# design.net
KiCad netlist of a schematic drawn in Altium Designer
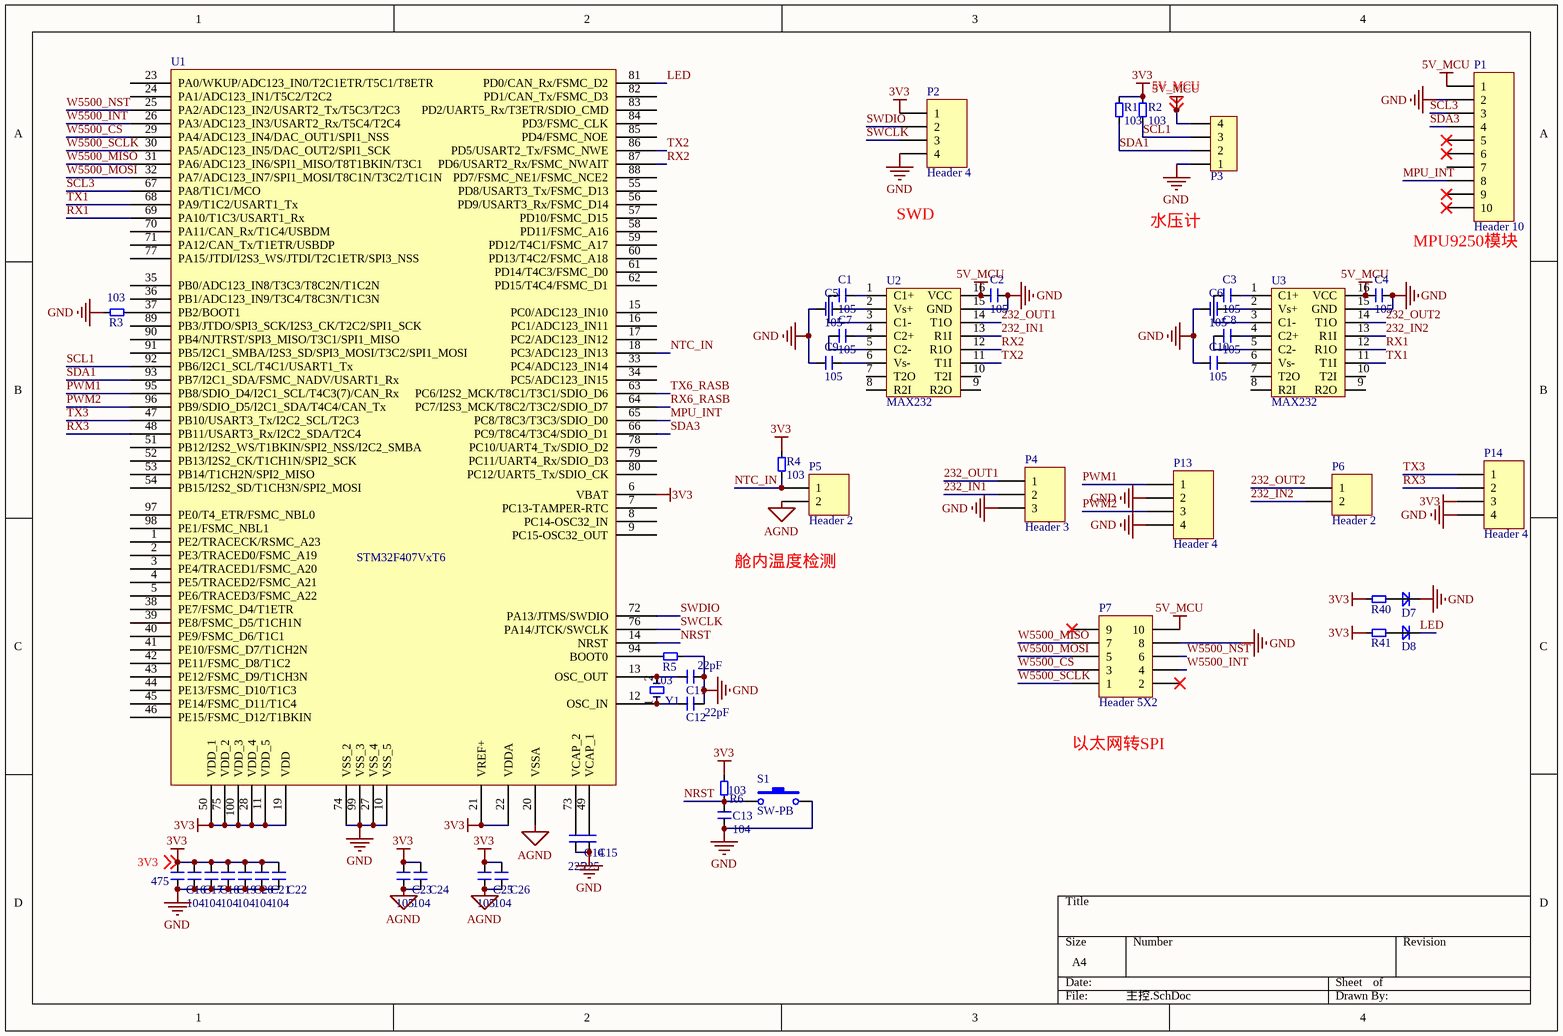
[diagram p0: 主控.SchDoc]

(export (version "E")
  (design (tool "Eeschema 10.0.6"))
  (components
    (comp (ref "C1")
      (value "0603C")
      (footprint "0603C")
      (fields (field (name "PARAMETER 1") "105"))
      (libsource (lib "水下去机器人控制板2020") (part "0603C"))
    )
    (comp (ref "C2")
      (value "0603C")
      (footprint "0603C")
      (fields (field (name "PARAMETER 1") "105"))
      (libsource (lib "水下去机器人控制板2020") (part "0603C"))
    )
    (comp (ref "C3")
      (value "0603C")
      (footprint "0603C")
      (fields (field (name "PARAMETER 1") "105"))
      (libsource (lib "水下去机器人控制板2020") (part "0603C"))
    )
    (comp (ref "C4")
      (value "0603C")
      (footprint "0603C")
      (fields (field (name "PARAMETER 1") "105"))
      (libsource (lib "水下去机器人控制板2020") (part "0603C"))
    )
    (comp (ref "C5")
      (value "0603C")
      (footprint "0603C")
      (fields (field (name "PARAMETER 1") "105"))
      (libsource (lib "水下去机器人控制板2020") (part "0603C"))
    )
    (comp (ref "C6")
      (value "0603C")
      (footprint "0603C")
      (fields (field (name "PARAMETER 1") "105"))
      (libsource (lib "水下去机器人控制板2020") (part "0603C"))
    )
    (comp (ref "C7")
      (value "0603C")
      (footprint "0603C")
      (fields (field (name "PARAMETER 1") "105"))
      (libsource (lib "水下去机器人控制板2020") (part "0603C"))
    )
    (comp (ref "C8")
      (value "0603C")
      (footprint "0603C")
      (fields (field (name "PARAMETER 1") "105"))
      (libsource (lib "水下去机器人控制板2020") (part "0603C"))
    )
    (comp (ref "C9")
      (value "0603C")
      (footprint "0603C")
      (fields (field (name "PARAMETER 1") "105"))
      (libsource (lib "水下去机器人控制板2020") (part "0603C"))
    )
    (comp (ref "C10")
      (value "0603C")
      (footprint "0603C")
      (fields (field (name "PARAMETER 1") "105"))
      (libsource (lib "水下去机器人控制板2020") (part "0603C"))
    )
    (comp (ref "C11")
      (value "0603C")
      (footprint "0603C")
      (fields (field (name "PARAMETER 1") "22pF"))
      (libsource (lib "水下去机器人控制板2020") (part "0603C"))
    )
    (comp (ref "C12")
      (value "0603C")
      (footprint "0603C")
      (fields (field (name "PARAMETER 1") "22pF"))
      (libsource (lib "水下去机器人控制板2020") (part "0603C"))
    )
    (comp (ref "C13")
      (value "0603C")
      (footprint "0603C")
      (fields (field (name "PARAMETER 1") "104"))
      (libsource (lib "水下去机器人控制板2020") (part "0603C"))
    )
    (comp (ref "C14")
      (value "0603C")
      (footprint "0603C")
      (fields (field (name "PARAMETER 1") "225"))
      (libsource (lib "水下去机器人控制板2020") (part "0603C"))
    )
    (comp (ref "C15")
      (value "0603C")
      (footprint "0603C")
      (fields (field (name "PARAMETER 1") "225"))
      (libsource (lib "水下去机器人控制板2020") (part "0603C"))
    )
    (comp (ref "C16")
      (value "0603C")
      (footprint "0603C")
      (fields (field (name "PARAMETER 1") "475"))
      (libsource (lib "水下去机器人控制板2020") (part "0603C"))
    )
    (comp (ref "C17")
      (value "0603C")
      (footprint "0603C")
      (fields (field (name "PARAMETER 1") "104"))
      (libsource (lib "水下去机器人控制板2020") (part "0603C"))
    )
    (comp (ref "C18")
      (value "0603C")
      (footprint "0603C")
      (fields (field (name "PARAMETER 1") "104"))
      (libsource (lib "水下去机器人控制板2020") (part "0603C"))
    )
    (comp (ref "C19")
      (value "0603C")
      (footprint "0603C")
      (fields (field (name "PARAMETER 1") "104"))
      (libsource (lib "水下去机器人控制板2020") (part "0603C"))
    )
    (comp (ref "C20")
      (value "0603C")
      (footprint "0603C")
      (fields (field (name "PARAMETER 1") "104"))
      (libsource (lib "水下去机器人控制板2020") (part "0603C"))
    )
    (comp (ref "C21")
      (value "0603C")
      (footprint "0603C")
      (fields (field (name "PARAMETER 1") "104"))
      (libsource (lib "水下去机器人控制板2020") (part "0603C"))
    )
    (comp (ref "C22")
      (value "0603C")
      (footprint "0603C")
      (fields (field (name "PARAMETER 1") "104"))
      (libsource (lib "水下去机器人控制板2020") (part "0603C"))
    )
    (comp (ref "C23")
      (value "0603C")
      (footprint "0603C")
      (fields (field (name "PARAMETER 1") "105"))
      (libsource (lib "水下去机器人控制板2020") (part "0603C"))
    )
    (comp (ref "C24")
      (value "0603C")
      (footprint "0603C")
      (fields (field (name "PARAMETER 1") "104"))
      (libsource (lib "水下去机器人控制板2020") (part "0603C"))
    )
    (comp (ref "C25")
      (value "0603C")
      (footprint "0603C")
      (fields (field (name "PARAMETER 1") "105"))
      (libsource (lib "水下去机器人控制板2020") (part "0603C"))
    )
    (comp (ref "C26")
      (value "0603C")
      (footprint "0603C")
      (fields (field (name "PARAMETER 1") "104"))
      (libsource (lib "水下去机器人控制板2020") (part "0603C"))
    )
    (comp (ref "D7") (value "0603D") (footprint "0603D") (libsource (lib "水下去机器人控制板2020") (part "0603D")))
    (comp (ref "D8") (value "0603D") (footprint "0603D") (libsource (lib "水下去机器人控制板2020") (part "0603D")))
    (comp (ref "P1")
      (value "Header 10")
      (footprint "HDR1X10")
      (description "Header, 10-Pin")
      (fields (field (name "PUBLISHER") "Altium Limited"))
      (libsource (lib "Miscellaneous Connectors") (part "Header 10"))
    )
    (comp (ref "P2")
      (value "Header 4")
      (footprint "HDR1X4")
      (description "Header, 4-Pin")
      (fields (field (name "PUBLISHER") "Altium Limited"))
      (libsource (lib "Miscellaneous Connectors") (part "Header 4"))
    )
    (comp (ref "P3")
      (value "1.27mm-4p")
      (footprint "1.27mm-4P")
      (libsource (lib "ROV_Schlib") (part "1.27mm-4p"))
    )
    (comp (ref "P4")
      (value "Header 3")
      (footprint "DB129-3")
      (description "Header, 3-Pin")
      (fields (field (name "PUBLISHER") "Altium Limited"))
      (libsource (lib "Miscellaneous Connectors") (part "Header 3"))
    )
    (comp (ref "P5")
      (value "Header 2")
      (footprint "HDR1X2")
      (description "Header, 2-Pin")
      (fields (field (name "PUBLISHER") "Altium Limited"))
      (libsource (lib "Miscellaneous Connectors") (part "Header 2"))
    )
    (comp (ref "P6")
      (value "Header 2")
      (footprint "DB129")
      (description "Header, 2-Pin")
      (fields (field (name "PUBLISHER") "Altium Limited"))
      (libsource (lib "Miscellaneous Connectors") (part "Header 2"))
    )
    (comp (ref "P7")
      (value "Header 5X2")
      (footprint "HDR2X5")
      (description "Header, 5-Pin, Dual row")
      (fields (field (name "PUBLISHER") "Altium Limited"))
      (libsource (lib "Miscellaneous Connectors") (part "Header 5X2"))
    )
    (comp (ref "P13")
      (value "Header 4")
      (footprint "HDR1X4")
      (description "Header, 4-Pin")
      (fields (field (name "PUBLISHER") "Altium Limited"))
      (libsource (lib "Miscellaneous Connectors") (part "Header 4"))
    )
    (comp (ref "P14")
      (value "Header 4")
      (footprint "HDR1X4")
      (description "Header, 4-Pin")
      (fields (field (name "PUBLISHER") "Altium Limited"))
      (libsource (lib "Miscellaneous Connectors") (part "Header 4"))
    )
    (comp (ref "R1")
      (value "0603R")
      (footprint "0603R")
      (fields (field (name "PARAMETER 1") "103"))
      (libsource (lib "水下去机器人控制板2020") (part "0603R"))
    )
    (comp (ref "R2")
      (value "0603R")
      (footprint "0603R")
      (fields (field (name "PARAMETER 1") "103"))
      (libsource (lib "水下去机器人控制板2020") (part "0603R"))
    )
    (comp (ref "R3")
      (value "0603R")
      (footprint "0603R")
      (fields (field (name "PARAMETER 1") "103"))
      (libsource (lib "水下去机器人控制板2020") (part "0603R"))
    )
    (comp (ref "R4")
      (value "0603R")
      (footprint "0603R")
      (fields (field (name "PARAMETER 1") "103"))
      (libsource (lib "水下去机器人控制板2020") (part "0603R"))
    )
    (comp (ref "R5")
      (value "0603R")
      (footprint "0603R")
      (fields (field (name "PARAMETER 1") "103"))
      (libsource (lib "水下去机器人控制板2020") (part "0603R"))
    )
    (comp (ref "R6")
      (value "0603R")
      (footprint "0603R")
      (fields (field (name "PARAMETER 1") "103"))
      (libsource (lib "水下去机器人控制板2020") (part "0603R"))
    )
    (comp (ref "R40") (value "0603R") (footprint "0603R") (libsource (lib "水下去机器人控制板2020") (part "0603R")))
    (comp (ref "R41") (value "0603R") (footprint "0603R") (libsource (lib "水下去机器人控制板2020") (part "0603R")))
    (comp (ref "S1")
      (value "SW-PB")
      (footprint "按键 3x6")
      (description "Switch")
      (fields (field (name "PUBLISHER") "Altium Limited"))
      (libsource (lib "Miscellaneous Devices") (part "SW-PB"))
    )
    (comp (ref "U1")
      (value "STM32F407VxT6")
      (footprint "LQFP-100_M")
      (libsource (lib "水下去机器人控制板2020") (part "STM32F407VxT6"))
    )
    (comp (ref "U2") (value "MAX232") (footprint "SOP16") (libsource (lib "CH340转232") (part "MAX232")))
    (comp (ref "U3") (value "MAX232") (footprint "SOP16") (libsource (lib "CH340转232") (part "MAX232")))
    (comp (ref "Y1")
      (value "XTAL_5032")
      (footprint "XTAL贴片")
      (libsource (lib "水下去机器人控制板2020") (part "XTAL_5032"))
    )
  )
  (nets
    (net (code "1") (name "/232_IN1") (class "Default")
      (node (ref "P4") (pin "2") (pinfunction "2_2") (pintype "passive"))
      (node (ref "U2") (pin "13") (pinfunction "R1I_13") (pintype "passive"))
    )
    (net (code "2") (name "/232_IN2") (class "Default")
      (node (ref "P6") (pin "2") (pinfunction "2_2") (pintype "passive"))
      (node (ref "U3") (pin "13") (pinfunction "R1I_13") (pintype "passive"))
    )
    (net (code "3") (name "/232_OUT1") (class "Default")
      (node (ref "P4") (pin "1") (pinfunction "1_1") (pintype "passive"))
      (node (ref "U2") (pin "14") (pinfunction "T1O_14") (pintype "passive"))
    )
    (net (code "4") (name "/232_OUT2") (class "Default")
      (node (ref "P6") (pin "1") (pinfunction "1_1") (pintype "passive"))
      (node (ref "U3") (pin "14") (pinfunction "T1O_14") (pintype "passive"))
    )
    (net (code "5") (name "/LED") (class "Default")
      (node (ref "D8") (pin "2") (pinfunction "2_2") (pintype "passive"))
      (node (ref "U1") (pin "81") (pinfunction "PD0/CAN_Rx/FSMC_D2_81") (pintype "passive"))
    )
    (net (code "6") (name "/MPU_INT") (class "Default")
      (node (ref "P1") (pin "8") (pinfunction "8_8") (pintype "passive"))
      (node (ref "U1") (pin "65") (pinfunction "PC8/T8C3/T3C3/SDIO_D0_65") (pintype "passive"))
    )
    (net (code "7") (name "/NRST") (class "Default")
      (node (ref "C13") (pin "2") (pinfunction "2_2") (pintype "passive"))
      (node (ref "R6") (pin "1") (pinfunction "1_1") (pintype "passive"))
      (node (ref "S1") (pin "1") (pinfunction "1_1") (pintype "passive"))
      (node (ref "U1") (pin "14") (pinfunction "NRST_14") (pintype "passive"))
    )
    (net (code "8") (name "/NTC_IN") (class "Default")
      (node (ref "P5") (pin "1") (pinfunction "1_1") (pintype "passive"))
      (node (ref "R4") (pin "1") (pinfunction "1_1") (pintype "passive"))
      (node (ref "U1") (pin "18") (pinfunction "PC3/ADC123_IN13_18") (pintype "passive"))
    )
    (net (code "9") (name "/PWM1") (class "Default")
      (node (ref "P13") (pin "1") (pinfunction "1_1") (pintype "passive"))
      (node (ref "U1") (pin "95") (pinfunction "PB8/SDIO_D4/I2C1_SCL/T4C3(7)/CAN_Rx_95") (pintype "passive"))
    )
    (net (code "10") (name "/PWM2") (class "Default")
      (node (ref "P13") (pin "3") (pinfunction "3_3") (pintype "passive"))
      (node (ref "U1") (pin "96") (pinfunction "PB9/SDIO_D5/I2C1_SDA/T4C4/CAN_Tx_96") (pintype "passive"))
    )
    (net (code "11") (name "/RX1") (class "Default")
      (node (ref "U1") (pin "69") (pinfunction "PA10/T1C3/USART1_Rx_69") (pintype "passive"))
      (node (ref "U3") (pin "12") (pinfunction "R1O_12") (pintype "passive"))
    )
    (net (code "12") (name "/RX2") (class "Default")
      (node (ref "U1") (pin "87") (pinfunction "PD6/USART2_Rx/FSMC_NWAIT_87") (pintype "passive"))
      (node (ref "U2") (pin "12") (pinfunction "R1O_12") (pintype "passive"))
    )
    (net (code "13") (name "/RX3") (class "Default")
      (node (ref "P14") (pin "2") (pinfunction "2_2") (pintype "passive"))
      (node (ref "U1") (pin "48") (pinfunction "PB11/USART3_Rx/I2C2_SDA/T2C4_48") (pintype "passive"))
    )
    (net (code "14") (name "/RX6_RASB") (class "Default")
      (node (ref "U1") (pin "64") (pinfunction "PC7/I2S3_MCK/T8C2/T3C2/SDIO_D7_64") (pintype "passive"))
    )
    (net (code "15") (name "/SCL1") (class "Default")
      (node (ref "P3") (pin "3") (pinfunction "3_3") (pintype "passive"))
      (node (ref "R2") (pin "1") (pinfunction "1_1") (pintype "passive"))
      (node (ref "U1") (pin "92") (pinfunction "PB6/I2C1_SCL/T4C1/USART1_Tx_92") (pintype "passive"))
    )
    (net (code "16") (name "/SCL3") (class "Default")
      (node (ref "P1") (pin "3") (pinfunction "3_3") (pintype "passive"))
      (node (ref "U1") (pin "67") (pinfunction "PA8/T1C1/MCO_67") (pintype "passive"))
    )
    (net (code "17") (name "/SDA1") (class "Default")
      (node (ref "P3") (pin "2") (pinfunction "2_2") (pintype "passive"))
      (node (ref "R1") (pin "1") (pinfunction "1_1") (pintype "passive"))
      (node (ref "U1") (pin "93") (pinfunction "PB7/I2C1_SDA/FSMC_NADV/USART1_Rx_93") (pintype "passive"))
    )
    (net (code "18") (name "/SDA3") (class "Default")
      (node (ref "P1") (pin "4") (pinfunction "4_4") (pintype "passive"))
      (node (ref "U1") (pin "66") (pinfunction "PC9/T8C4/T3C4/SDIO_D1_66") (pintype "passive"))
    )
    (net (code "19") (name "/SWCLK") (class "Default")
      (node (ref "P2") (pin "3") (pinfunction "3_3") (pintype "passive"))
      (node (ref "U1") (pin "76") (pinfunction "PA14/JTCK/SWCLK_76") (pintype "passive"))
    )
    (net (code "20") (name "/SWDIO") (class "Default")
      (node (ref "P2") (pin "2") (pinfunction "2_2") (pintype "passive"))
      (node (ref "U1") (pin "72") (pinfunction "PA13/JTMS/SWDIO_72") (pintype "passive"))
    )
    (net (code "21") (name "/TX1") (class "Default")
      (node (ref "U1") (pin "68") (pinfunction "PA9/T1C2/USART1_Tx_68") (pintype "passive"))
      (node (ref "U3") (pin "11") (pinfunction "T1I_11") (pintype "passive"))
    )
    (net (code "22") (name "/TX2") (class "Default")
      (node (ref "U1") (pin "86") (pinfunction "PD5/USART2_Tx/FSMC_NWE_86") (pintype "passive"))
      (node (ref "U2") (pin "11") (pinfunction "T1I_11") (pintype "passive"))
    )
    (net (code "23") (name "/TX3") (class "Default")
      (node (ref "P14") (pin "1") (pinfunction "1_1") (pintype "passive"))
      (node (ref "U1") (pin "47") (pinfunction "PB10/USART3_Tx/I2C2_SCL/T2C3_47") (pintype "passive"))
    )
    (net (code "24") (name "/TX6_RASB") (class "Default")
      (node (ref "U1") (pin "63") (pinfunction "PC6/I2S2_MCK/T8C1/T3C1/SDIO_D6_63") (pintype "passive"))
    )
    (net (code "25") (name "/W5500_CS") (class "Default")
      (node (ref "P7") (pin "3") (pinfunction "3_3") (pintype "passive"))
      (node (ref "U1") (pin "29") (pinfunction "PA4/ADC123_IN4/DAC_OUT1/SPI1_NSS_29") (pintype "passive"))
    )
    (net (code "26") (name "/W5500_INT") (class "Default")
      (node (ref "P7") (pin "4") (pinfunction "4_4") (pintype "passive"))
      (node (ref "U1") (pin "26") (pinfunction "PA3/ADC123_IN3/USART2_Rx/T5C4/T2C4_26") (pintype "passive"))
    )
    (net (code "27") (name "/W5500_MISO") (class "Default")
      (node (ref "P7") (pin "7") (pinfunction "7_7") (pintype "passive"))
      (node (ref "U1") (pin "31") (pinfunction "PA6/ADC123_IN6/SPI1_MISO/T8T1BKIN/T3C1_31") (pintype "passive"))
    )
    (net (code "28") (name "/W5500_MOSI") (class "Default")
      (node (ref "P7") (pin "5") (pinfunction "5_5") (pintype "passive"))
      (node (ref "U1") (pin "32") (pinfunction "PA7/ADC123_IN7/SPI1_MOSI/T8C1N/T3C2/T1C1N_32") (pintype "passive"))
    )
    (net (code "29") (name "/W5500_NST") (class "Default")
      (node (ref "P7") (pin "6") (pinfunction "6_6") (pintype "passive"))
      (node (ref "U1") (pin "25") (pinfunction "PA2/ADC123_IN2/USART2_Tx/T5C3/T2C3_25") (pintype "passive"))
    )
    (net (code "30") (name "/W5500_SCLK") (class "Default")
      (node (ref "P7") (pin "1") (pinfunction "1_1") (pintype "passive"))
      (node (ref "U1") (pin "30") (pinfunction "PA5/ADC123_IN5/DAC_OUT2/SPI1_SCK_30") (pintype "passive"))
    )
    (net (code "31") (name "3V3") (class "Default")
      (node (ref "C16") (pin "2") (pinfunction "2_2") (pintype "passive"))
      (node (ref "C17") (pin "2") (pinfunction "2_2") (pintype "passive"))
      (node (ref "C18") (pin "2") (pinfunction "2_2") (pintype "passive"))
      (node (ref "C19") (pin "2") (pinfunction "2_2") (pintype "passive"))
      (node (ref "C20") (pin "2") (pinfunction "2_2") (pintype "passive"))
      (node (ref "C21") (pin "2") (pinfunction "2_2") (pintype "passive"))
      (node (ref "C22") (pin "2") (pinfunction "2_2") (pintype "passive"))
      (node (ref "C23") (pin "2") (pinfunction "2_2") (pintype "passive"))
      (node (ref "C24") (pin "2") (pinfunction "2_2") (pintype "passive"))
      (node (ref "C25") (pin "1") (pinfunction "1_1") (pintype "passive"))
      (node (ref "C26") (pin "1") (pinfunction "1_1") (pintype "passive"))
      (node (ref "P14") (pin "3") (pinfunction "3_3") (pintype "passive"))
      (node (ref "P2") (pin "1") (pinfunction "1_1") (pintype "passive"))
      (node (ref "R1") (pin "2") (pinfunction "2_2") (pintype "passive"))
      (node (ref "R2") (pin "2") (pinfunction "2_2") (pintype "passive"))
      (node (ref "R4") (pin "2") (pinfunction "2_2") (pintype "passive"))
      (node (ref "R40") (pin "1") (pinfunction "1_1") (pintype "passive"))
      (node (ref "R41") (pin "1") (pinfunction "1_1") (pintype "passive"))
      (node (ref "R6") (pin "2") (pinfunction "2_2") (pintype "passive"))
      (node (ref "U1") (pin "100") (pinfunction "VDD_3_100") (pintype "passive"))
      (node (ref "U1") (pin "11") (pinfunction "VDD_5_11") (pintype "passive"))
      (node (ref "U1") (pin "19") (pinfunction "VDD_19") (pintype "passive"))
      (node (ref "U1") (pin "21") (pinfunction "VREF+_21") (pintype "passive"))
      (node (ref "U1") (pin "22") (pinfunction "VDDA_22") (pintype "passive"))
      (node (ref "U1") (pin "28") (pinfunction "VDD_4_28") (pintype "passive"))
      (node (ref "U1") (pin "50") (pinfunction "VDD_1_50") (pintype "passive"))
      (node (ref "U1") (pin "6") (pinfunction "VBAT_6") (pintype "passive"))
      (node (ref "U1") (pin "75") (pinfunction "VDD_2_75") (pintype "passive"))
    )
    (net (code "32") (name "5V_MCU") (class "Default")
      (node (ref "C2") (pin "1") (pinfunction "1_1") (pintype "passive"))
      (node (ref "C4") (pin "1") (pinfunction "1_1") (pintype "passive"))
      (node (ref "P1") (pin "1") (pinfunction "1_1") (pintype "passive"))
      (node (ref "P3") (pin "4") (pinfunction "4_4") (pintype "passive"))
      (node (ref "P7") (pin "10") (pinfunction "10_10") (pintype "passive"))
      (node (ref "U2") (pin "16") (pinfunction "VCC_16") (pintype "passive"))
      (node (ref "U3") (pin "16") (pinfunction "VCC_16") (pintype "passive"))
    )
    (net (code "33") (name "AGND") (class "Default")
      (node (ref "C23") (pin "1") (pinfunction "1_1") (pintype "passive"))
      (node (ref "C24") (pin "1") (pinfunction "1_1") (pintype "passive"))
      (node (ref "C25") (pin "2") (pinfunction "2_2") (pintype "passive"))
      (node (ref "C26") (pin "2") (pinfunction "2_2") (pintype "passive"))
      (node (ref "P5") (pin "2") (pinfunction "2_2") (pintype "passive"))
      (node (ref "U1") (pin "20") (pinfunction "VSSA_20") (pintype "passive"))
    )
    (net (code "34") (name "GND") (class "Default")
      (node (ref "C10") (pin "1") (pinfunction "1_1") (pintype "passive"))
      (node (ref "C11") (pin "2") (pinfunction "2_2") (pintype "passive"))
      (node (ref "C12") (pin "2") (pinfunction "2_2") (pintype "passive"))
      (node (ref "C13") (pin "1") (pinfunction "1_1") (pintype "passive"))
      (node (ref "C14") (pin "1") (pinfunction "1_1") (pintype "passive"))
      (node (ref "C15") (pin "1") (pinfunction "1_1") (pintype "passive"))
      (node (ref "C16") (pin "1") (pinfunction "1_1") (pintype "passive"))
      (node (ref "C17") (pin "1") (pinfunction "1_1") (pintype "passive"))
      (node (ref "C18") (pin "1") (pinfunction "1_1") (pintype "passive"))
      (node (ref "C19") (pin "1") (pinfunction "1_1") (pintype "passive"))
      (node (ref "C2") (pin "2") (pinfunction "2_2") (pintype "passive"))
      (node (ref "C20") (pin "1") (pinfunction "1_1") (pintype "passive"))
      (node (ref "C21") (pin "1") (pinfunction "1_1") (pintype "passive"))
      (node (ref "C22") (pin "1") (pinfunction "1_1") (pintype "passive"))
      (node (ref "C4") (pin "2") (pinfunction "2_2") (pintype "passive"))
      (node (ref "C5") (pin "1") (pinfunction "1_1") (pintype "passive"))
      (node (ref "C6") (pin "1") (pinfunction "1_1") (pintype "passive"))
      (node (ref "C9") (pin "1") (pinfunction "1_1") (pintype "passive"))
      (node (ref "D7") (pin "2") (pinfunction "2_2") (pintype "passive"))
      (node (ref "P1") (pin "2") (pinfunction "2_2") (pintype "passive"))
      (node (ref "P13") (pin "2") (pinfunction "2_2") (pintype "passive"))
      (node (ref "P13") (pin "4") (pinfunction "4_4") (pintype "passive"))
      (node (ref "P14") (pin "4") (pinfunction "4_4") (pintype "passive"))
      (node (ref "P2") (pin "4") (pinfunction "4_4") (pintype "passive"))
      (node (ref "P3") (pin "1") (pinfunction "1_1") (pintype "passive"))
      (node (ref "P4") (pin "3") (pinfunction "3_3") (pintype "passive"))
      (node (ref "P7") (pin "8") (pinfunction "8_8") (pintype "passive"))
      (node (ref "R3") (pin "1") (pinfunction "1_1") (pintype "passive"))
      (node (ref "R5") (pin "2") (pinfunction "2_2") (pintype "passive"))
      (node (ref "S1") (pin "2") (pinfunction "2_2") (pintype "passive"))
      (node (ref "U1") (pin "10") (pinfunction "VSS_5_10") (pintype "passive"))
      (node (ref "U1") (pin "27") (pinfunction "VSS_4_27") (pintype "passive"))
      (node (ref "U1") (pin "74") (pinfunction "VSS_2_74") (pintype "passive"))
      (node (ref "U1") (pin "99") (pinfunction "VSS_3_99") (pintype "passive"))
      (node (ref "U2") (pin "15") (pinfunction "GND_15") (pintype "passive"))
      (node (ref "U3") (pin "15") (pinfunction "GND_15") (pintype "passive"))
    )
    (net (code "35") (name "Net-(D7-Pad1)") (class "Default")
      (node (ref "D7") (pin "1") (pinfunction "1_1") (pintype "passive"))
      (node (ref "R40") (pin "2") (pinfunction "2_2") (pintype "passive"))
    )
    (net (code "36") (name "Net-(D8-Pad1)") (class "Default")
      (node (ref "D8") (pin "1") (pinfunction "1_1") (pintype "passive"))
      (node (ref "R41") (pin "2") (pinfunction "2_2") (pintype "passive"))
    )
    (net (code "37") (name "Net-(U1-BOOT0)") (class "Default")
      (node (ref "R5") (pin "1") (pinfunction "1_1") (pintype "passive"))
      (node (ref "U1") (pin "94") (pinfunction "BOOT0_94") (pintype "passive"))
    )
    (net (code "38") (name "Net-(U1-OSC_IN)") (class "Default")
      (node (ref "C12") (pin "1") (pinfunction "1_1") (pintype "passive"))
      (node (ref "U1") (pin "12") (pinfunction "OSC_IN_12") (pintype "passive"))
      (node (ref "Y1") (pin "1") (pinfunction "1_1") (pintype "passive"))
    )
    (net (code "39") (name "Net-(U1-OSC_OUT)") (class "Default")
      (node (ref "C11") (pin "1") (pinfunction "1_1") (pintype "passive"))
      (node (ref "U1") (pin "13") (pinfunction "OSC_OUT_13") (pintype "passive"))
      (node (ref "Y1") (pin "2") (pinfunction "2_2") (pintype "passive"))
    )
    (net (code "40") (name "Net-(U1-PB2{slash}BOOT1)") (class "Default")
      (node (ref "R3") (pin "2") (pinfunction "2_2") (pintype "passive"))
      (node (ref "U1") (pin "37") (pinfunction "PB2/BOOT1_37") (pintype "passive"))
    )
    (net (code "41") (name "Net-(U1-VCAP_1)") (class "Default")
      (node (ref "C15") (pin "2") (pinfunction "2_2") (pintype "passive"))
      (node (ref "U1") (pin "49") (pinfunction "VCAP_1_49") (pintype "passive"))
    )
    (net (code "42") (name "Net-(U1-VCAP_2)") (class "Default")
      (node (ref "C14") (pin "2") (pinfunction "2_2") (pintype "passive"))
      (node (ref "U1") (pin "73") (pinfunction "VCAP_2_73") (pintype "passive"))
    )
    (net (code "43") (name "Net-(U2-C1+)") (class "Default")
      (node (ref "C1") (pin "2") (pinfunction "2_2") (pintype "passive"))
      (node (ref "U2") (pin "1") (pinfunction "C1+_1") (pintype "passive"))
    )
    (net (code "44") (name "Net-(U2-C1-)") (class "Default")
      (node (ref "C1") (pin "1") (pinfunction "1_1") (pintype "passive"))
      (node (ref "U2") (pin "3") (pinfunction "C1-_3") (pintype "passive"))
    )
    (net (code "45") (name "Net-(U2-C2+)") (class "Default")
      (node (ref "C7") (pin "2") (pinfunction "2_2") (pintype "passive"))
      (node (ref "U2") (pin "4") (pinfunction "C2+_4") (pintype "passive"))
    )
    (net (code "46") (name "Net-(U2-C2-)") (class "Default")
      (node (ref "C7") (pin "1") (pinfunction "1_1") (pintype "passive"))
      (node (ref "U2") (pin "5") (pinfunction "C2-_5") (pintype "passive"))
    )
    (net (code "47") (name "Net-(U2-Vs+)") (class "Default")
      (node (ref "C5") (pin "2") (pinfunction "2_2") (pintype "passive"))
      (node (ref "U2") (pin "2") (pinfunction "Vs+_2") (pintype "passive"))
    )
    (net (code "48") (name "Net-(U2-Vs-)") (class "Default")
      (node (ref "C9") (pin "2") (pinfunction "2_2") (pintype "passive"))
      (node (ref "U2") (pin "6") (pinfunction "Vs-_6") (pintype "passive"))
    )
    (net (code "49") (name "Net-(U3-C1+)") (class "Default")
      (node (ref "C3") (pin "2") (pinfunction "2_2") (pintype "passive"))
      (node (ref "U3") (pin "1") (pinfunction "C1+_1") (pintype "passive"))
    )
    (net (code "50") (name "Net-(U3-C1-)") (class "Default")
      (node (ref "C3") (pin "1") (pinfunction "1_1") (pintype "passive"))
      (node (ref "U3") (pin "3") (pinfunction "C1-_3") (pintype "passive"))
    )
    (net (code "51") (name "Net-(U3-C2+)") (class "Default")
      (node (ref "C8") (pin "2") (pinfunction "2_2") (pintype "passive"))
      (node (ref "U3") (pin "4") (pinfunction "C2+_4") (pintype "passive"))
    )
    (net (code "52") (name "Net-(U3-C2-)") (class "Default")
      (node (ref "C8") (pin "1") (pinfunction "1_1") (pintype "passive"))
      (node (ref "U3") (pin "5") (pinfunction "C2-_5") (pintype "passive"))
    )
    (net (code "53") (name "Net-(U3-Vs+)") (class "Default")
      (node (ref "C6") (pin "2") (pinfunction "2_2") (pintype "passive"))
      (node (ref "U3") (pin "2") (pinfunction "Vs+_2") (pintype "passive"))
    )
    (net (code "54") (name "Net-(U3-Vs-)") (class "Default")
      (node (ref "C10") (pin "2") (pinfunction "2_2") (pintype "passive"))
      (node (ref "U3") (pin "6") (pinfunction "Vs-_6") (pintype "passive"))
    )
    (net (code "55") (name "unconnected-(P1-Pad5)") (class "Default")
      (node (ref "P1") (pin "5") (pinfunction "5_5") (pintype "passive+no_connect"))
    )
    (net (code "56") (name "unconnected-(P1-Pad6)") (class "Default")
      (node (ref "P1") (pin "6") (pinfunction "6_6") (pintype "passive+no_connect"))
    )
    (net (code "57") (name "unconnected-(P1-Pad7)") (class "Default")
      (node (ref "P1") (pin "7") (pinfunction "7_7") (pintype "passive"))
    )
    (net (code "58") (name "unconnected-(P1-Pad9)") (class "Default")
      (node (ref "P1") (pin "9") (pinfunction "9_9") (pintype "passive+no_connect"))
    )
    (net (code "59") (name "unconnected-(P1-Pad10)") (class "Default")
      (node (ref "P1") (pin "10") (pinfunction "10_10") (pintype "passive+no_connect"))
    )
    (net (code "60") (name "unconnected-(P7-Pad2)") (class "Default")
      (node (ref "P7") (pin "2") (pinfunction "2_2") (pintype "passive+no_connect"))
    )
    (net (code "61") (name "unconnected-(P7-Pad9)") (class "Default")
      (node (ref "P7") (pin "9") (pinfunction "9_9") (pintype "passive+no_connect"))
    )
    (net (code "62") (name "unconnected-(U1-PA0{slash}WKUP{slash}ADC123_IN0{slash}T2C1ETR{slash}T5C1{slash}T8ETR-Pad23)") (class "Default")
      (node (ref "U1") (pin "23") (pinfunction "PA0/WKUP/ADC123_IN0/T2C1ETR/T5C1/T8ETR_23") (pintype "passive"))
    )
    (net (code "63") (name "unconnected-(U1-PA1{slash}ADC123_IN1{slash}T5C2{slash}T2C2-Pad24)") (class "Default")
      (node (ref "U1") (pin "24") (pinfunction "PA1/ADC123_IN1/T5C2/T2C2_24") (pintype "passive"))
    )
    (net (code "64") (name "unconnected-(U1-PA11{slash}CAN_Rx{slash}T1C4{slash}USBDM-Pad70)") (class "Default")
      (node (ref "U1") (pin "70") (pinfunction "PA11/CAN_Rx/T1C4/USBDM_70") (pintype "passive"))
    )
    (net (code "65") (name "unconnected-(U1-PA12{slash}CAN_Tx{slash}T1ETR{slash}USBDP-Pad71)") (class "Default")
      (node (ref "U1") (pin "71") (pinfunction "PA12/CAN_Tx/T1ETR/USBDP_71") (pintype "passive"))
    )
    (net (code "66") (name "unconnected-(U1-PA15{slash}JTDI{slash}I2S3_WS{slash}JTDI{slash}T2C1ETR{slash}SPI3_NSS-Pad77)") (class "Default")
      (node (ref "U1") (pin "77") (pinfunction "PA15/JTDI/I2S3_WS/JTDI/T2C1ETR/SPI3_NSS_77") (pintype "passive"))
    )
    (net (code "67") (name "unconnected-(U1-PB0{slash}ADC123_IN8{slash}T3C3{slash}T8C2N{slash}T1C2N-Pad35)") (class "Default")
      (node (ref "U1") (pin "35") (pinfunction "PB0/ADC123_IN8/T3C3/T8C2N/T1C2N_35") (pintype "passive"))
    )
    (net (code "68") (name "unconnected-(U1-PB1{slash}ADC123_IN9{slash}T3C4{slash}T8C3N{slash}T1C3N-Pad36)") (class "Default")
      (node (ref "U1") (pin "36") (pinfunction "PB1/ADC123_IN9/T3C4/T8C3N/T1C3N_36") (pintype "passive"))
    )
    (net (code "69") (name "unconnected-(U1-PB3{slash}JTDO{slash}SPI3_SCK{slash}I2S3_CK{slash}T2C2{slash}SPI1_SCK-Pad89)") (class "Default")
      (node (ref "U1") (pin "89") (pinfunction "PB3/JTDO/SPI3_SCK/I2S3_CK/T2C2/SPI1_SCK_89") (pintype "passive"))
    )
    (net (code "70") (name "unconnected-(U1-PB4{slash}NJTRST{slash}SPI3_MISO{slash}T3C1{slash}SPI1_MISO-Pad90)") (class "Default")
      (node (ref "U1") (pin "90") (pinfunction "PB4/NJTRST/SPI3_MISO/T3C1/SPI1_MISO_90") (pintype "passive"))
    )
    (net (code "71") (name "unconnected-(U1-PB5{slash}I2C1_SMBA{slash}I2S3_SD{slash}SPI3_MOSI{slash}T3C2{slash}SPI1_MOSI-Pad91)") (class "Default")
      (node (ref "U1") (pin "91") (pinfunction "PB5/I2C1_SMBA/I2S3_SD/SPI3_MOSI/T3C2/SPI1_MOSI_91") (pintype "passive"))
    )
    (net (code "72") (name "unconnected-(U1-PB12{slash}I2S2_WS{slash}T1BKIN{slash}SPI2_NSS{slash}I2C2_SMBA-Pad51)") (class "Default")
      (node (ref "U1") (pin "51") (pinfunction "PB12/I2S2_WS/T1BKIN/SPI2_NSS/I2C2_SMBA_51") (pintype "passive"))
    )
    (net (code "73") (name "unconnected-(U1-PB13{slash}I2S2_CK{slash}T1CH1N{slash}SPI2_SCK-Pad52)") (class "Default")
      (node (ref "U1") (pin "52") (pinfunction "PB13/I2S2_CK/T1CH1N/SPI2_SCK_52") (pintype "passive"))
    )
    (net (code "74") (name "unconnected-(U1-PB14{slash}T1CH2N{slash}SPI2_MISO-Pad53)") (class "Default")
      (node (ref "U1") (pin "53") (pinfunction "PB14/T1CH2N/SPI2_MISO_53") (pintype "passive"))
    )
    (net (code "75") (name "unconnected-(U1-PB15{slash}I2S2_SD{slash}T1CH3N{slash}SPI2_MOSI-Pad54)") (class "Default")
      (node (ref "U1") (pin "54") (pinfunction "PB15/I2S2_SD/T1CH3N/SPI2_MOSI_54") (pintype "passive"))
    )
    (net (code "76") (name "unconnected-(U1-PC0{slash}ADC123_IN10-Pad15)") (class "Default")
      (node (ref "U1") (pin "15") (pinfunction "PC0/ADC123_IN10_15") (pintype "passive"))
    )
    (net (code "77") (name "unconnected-(U1-PC1{slash}ADC123_IN11-Pad16)") (class "Default")
      (node (ref "U1") (pin "16") (pinfunction "PC1/ADC123_IN11_16") (pintype "passive"))
    )
    (net (code "78") (name "unconnected-(U1-PC2{slash}ADC123_IN12-Pad17)") (class "Default")
      (node (ref "U1") (pin "17") (pinfunction "PC2/ADC123_IN12_17") (pintype "passive"))
    )
    (net (code "79") (name "unconnected-(U1-PC4{slash}ADC123_IN14-Pad33)") (class "Default")
      (node (ref "U1") (pin "33") (pinfunction "PC4/ADC123_IN14_33") (pintype "passive"))
    )
    (net (code "80") (name "unconnected-(U1-PC5{slash}ADC123_IN15-Pad34)") (class "Default")
      (node (ref "U1") (pin "34") (pinfunction "PC5/ADC123_IN15_34") (pintype "passive"))
    )
    (net (code "81") (name "unconnected-(U1-PC10{slash}UART4_Tx{slash}SDIO_D2-Pad78)") (class "Default")
      (node (ref "U1") (pin "78") (pinfunction "PC10/UART4_Tx/SDIO_D2_78") (pintype "passive"))
    )
    (net (code "82") (name "unconnected-(U1-PC11{slash}UART4_Rx{slash}SDIO_D3-Pad79)") (class "Default")
      (node (ref "U1") (pin "79") (pinfunction "PC11/UART4_Rx/SDIO_D3_79") (pintype "passive"))
    )
    (net (code "83") (name "unconnected-(U1-PC12{slash}UART5_Tx{slash}SDIO_CK-Pad80)") (class "Default")
      (node (ref "U1") (pin "80") (pinfunction "PC12/UART5_Tx/SDIO_CK_80") (pintype "passive"))
    )
    (net (code "84") (name "unconnected-(U1-PC13-TAMPER-RTC-Pad7)") (class "Default")
      (node (ref "U1") (pin "7") (pinfunction "PC13-TAMPER-RTC_7") (pintype "passive"))
    )
    (net (code "85") (name "unconnected-(U1-PC14-OSC32_IN-Pad8)") (class "Default")
      (node (ref "U1") (pin "8") (pinfunction "PC14-OSC32_IN_8") (pintype "passive"))
    )
    (net (code "86") (name "unconnected-(U1-PC15-OSC32_OUT-Pad9)") (class "Default")
      (node (ref "U1") (pin "9") (pinfunction "PC15-OSC32_OUT_9") (pintype "passive"))
    )
    (net (code "87") (name "unconnected-(U1-PD1{slash}CAN_Tx{slash}FSMC_D3-Pad82)") (class "Default")
      (node (ref "U1") (pin "82") (pinfunction "PD1/CAN_Tx/FSMC_D3_82") (pintype "passive"))
    )
    (net (code "88") (name "unconnected-(U1-PD2{slash}UART5_Rx{slash}T3ETR{slash}SDIO_CMD-Pad83)") (class "Default")
      (node (ref "U1") (pin "83") (pinfunction "PD2/UART5_Rx/T3ETR/SDIO_CMD_83") (pintype "passive"))
    )
    (net (code "89") (name "unconnected-(U1-PD3{slash}FSMC_CLK-Pad84)") (class "Default")
      (node (ref "U1") (pin "84") (pinfunction "PD3/FSMC_CLK_84") (pintype "passive"))
    )
    (net (code "90") (name "unconnected-(U1-PD4{slash}FSMC_NOE-Pad85)") (class "Default")
      (node (ref "U1") (pin "85") (pinfunction "PD4/FSMC_NOE_85") (pintype "passive"))
    )
    (net (code "91") (name "unconnected-(U1-PD7{slash}FSMC_NE1{slash}FSMC_NCE2-Pad88)") (class "Default")
      (node (ref "U1") (pin "88") (pinfunction "PD7/FSMC_NE1/FSMC_NCE2_88") (pintype "passive"))
    )
    (net (code "92") (name "unconnected-(U1-PD8{slash}USART3_Tx{slash}FSMC_D13-Pad55)") (class "Default")
      (node (ref "U1") (pin "55") (pinfunction "PD8/USART3_Tx/FSMC_D13_55") (pintype "passive"))
    )
    (net (code "93") (name "unconnected-(U1-PD9{slash}USART3_Rx{slash}FSMC_D14-Pad56)") (class "Default")
      (node (ref "U1") (pin "56") (pinfunction "PD9/USART3_Rx/FSMC_D14_56") (pintype "passive"))
    )
    (net (code "94") (name "unconnected-(U1-PD10{slash}FSMC_D15-Pad57)") (class "Default")
      (node (ref "U1") (pin "57") (pinfunction "PD10/FSMC_D15_57") (pintype "passive"))
    )
    (net (code "95") (name "unconnected-(U1-PD11{slash}FSMC_A16-Pad58)") (class "Default")
      (node (ref "U1") (pin "58") (pinfunction "PD11/FSMC_A16_58") (pintype "passive"))
    )
    (net (code "96") (name "unconnected-(U1-PD12{slash}T4C1{slash}FSMC_A17-Pad59)") (class "Default")
      (node (ref "U1") (pin "59") (pinfunction "PD12/T4C1/FSMC_A17_59") (pintype "passive"))
    )
    (net (code "97") (name "unconnected-(U1-PD13{slash}T4C2{slash}FSMC_A18-Pad60)") (class "Default")
      (node (ref "U1") (pin "60") (pinfunction "PD13/T4C2/FSMC_A18_60") (pintype "passive"))
    )
    (net (code "98") (name "unconnected-(U1-PD14{slash}T4C3{slash}FSMC_D0-Pad61)") (class "Default")
      (node (ref "U1") (pin "61") (pinfunction "PD14/T4C3/FSMC_D0_61") (pintype "passive"))
    )
    (net (code "99") (name "unconnected-(U1-PD15{slash}T4C4{slash}FSMC_D1-Pad62)") (class "Default")
      (node (ref "U1") (pin "62") (pinfunction "PD15/T4C4/FSMC_D1_62") (pintype "passive"))
    )
    (net (code "100") (name "unconnected-(U1-PE0{slash}T4_ETR{slash}FSMC_NBL0-Pad97)") (class "Default")
      (node (ref "U1") (pin "97") (pinfunction "PE0/T4_ETR/FSMC_NBL0_97") (pintype "passive"))
    )
    (net (code "101") (name "unconnected-(U1-PE1{slash}FSMC_NBL1-Pad98)") (class "Default")
      (node (ref "U1") (pin "98") (pinfunction "PE1/FSMC_NBL1_98") (pintype "passive"))
    )
    (net (code "102") (name "unconnected-(U1-PE2{slash}TRACECK{slash}RSMC_A23-Pad1)") (class "Default")
      (node (ref "U1") (pin "1") (pinfunction "PE2/TRACECK/RSMC_A23_1") (pintype "passive"))
    )
    (net (code "103") (name "unconnected-(U1-PE3{slash}TRACED0{slash}FSMC_A19-Pad2)") (class "Default")
      (node (ref "U1") (pin "2") (pinfunction "PE3/TRACED0/FSMC_A19_2") (pintype "passive"))
    )
    (net (code "104") (name "unconnected-(U1-PE4{slash}TRACED1{slash}FSMC_A20-Pad3)") (class "Default")
      (node (ref "U1") (pin "3") (pinfunction "PE4/TRACED1/FSMC_A20_3") (pintype "passive"))
    )
    (net (code "105") (name "unconnected-(U1-PE5{slash}TRACED2{slash}FSMC_A21-Pad4)") (class "Default")
      (node (ref "U1") (pin "4") (pinfunction "PE5/TRACED2/FSMC_A21_4") (pintype "passive"))
    )
    (net (code "106") (name "unconnected-(U1-PE6{slash}TRACED3{slash}FSMC_A22-Pad5)") (class "Default")
      (node (ref "U1") (pin "5") (pinfunction "PE6/TRACED3/FSMC_A22_5") (pintype "passive"))
    )
    (net (code "107") (name "unconnected-(U1-PE7{slash}FSMC_D4{slash}T1ETR-Pad38)") (class "Default")
      (node (ref "U1") (pin "38") (pinfunction "PE7/FSMC_D4/T1ETR_38") (pintype "passive"))
    )
    (net (code "108") (name "unconnected-(U1-PE8{slash}FSMC_D5{slash}T1CH1N-Pad39)") (class "Default")
      (node (ref "U1") (pin "39") (pinfunction "PE8/FSMC_D5/T1CH1N_39") (pintype "passive"))
    )
    (net (code "109") (name "unconnected-(U1-PE9{slash}FSMC_D6{slash}T1C1-Pad40)") (class "Default")
      (node (ref "U1") (pin "40") (pinfunction "PE9/FSMC_D6/T1C1_40") (pintype "passive"))
    )
    (net (code "110") (name "unconnected-(U1-PE10{slash}FSMC_D7{slash}T1CH2N-Pad41)") (class "Default")
      (node (ref "U1") (pin "41") (pinfunction "PE10/FSMC_D7/T1CH2N_41") (pintype "passive"))
    )
    (net (code "111") (name "unconnected-(U1-PE11{slash}FSMC_D8{slash}T1C2-Pad42)") (class "Default")
      (node (ref "U1") (pin "42") (pinfunction "PE11/FSMC_D8/T1C2_42") (pintype "passive"))
    )
    (net (code "112") (name "unconnected-(U1-PE12{slash}FSMC_D9{slash}T1CH3N-Pad43)") (class "Default")
      (node (ref "U1") (pin "43") (pinfunction "PE12/FSMC_D9/T1CH3N_43") (pintype "passive"))
    )
    (net (code "113") (name "unconnected-(U1-PE13{slash}FSMC_D10{slash}T1C3-Pad44)") (class "Default")
      (node (ref "U1") (pin "44") (pinfunction "PE13/FSMC_D10/T1C3_44") (pintype "passive"))
    )
    (net (code "114") (name "unconnected-(U1-PE14{slash}FSMC_D11{slash}T1C4-Pad45)") (class "Default")
      (node (ref "U1") (pin "45") (pinfunction "PE14/FSMC_D11/T1C4_45") (pintype "passive"))
    )
    (net (code "115") (name "unconnected-(U1-PE15{slash}FSMC_D12{slash}T1BKIN-Pad46)") (class "Default")
      (node (ref "U1") (pin "46") (pinfunction "PE15/FSMC_D12/T1BKIN_46") (pintype "passive"))
    )
    (net (code "116") (name "unconnected-(U2-R2I-Pad8)") (class "Default")
      (node (ref "U2") (pin "8") (pinfunction "R2I_8") (pintype "passive"))
    )
    (net (code "117") (name "unconnected-(U2-R2O-Pad9)") (class "Default")
      (node (ref "U2") (pin "9") (pinfunction "R2O_9") (pintype "passive"))
    )
    (net (code "118") (name "unconnected-(U2-T2I-Pad10)") (class "Default")
      (node (ref "U2") (pin "10") (pinfunction "T2I_10") (pintype "passive"))
    )
    (net (code "119") (name "unconnected-(U2-T2O-Pad7)") (class "Default")
      (node (ref "U2") (pin "7") (pinfunction "T2O_7") (pintype "passive"))
    )
    (net (code "120") (name "unconnected-(U3-R2I-Pad8)") (class "Default")
      (node (ref "U3") (pin "8") (pinfunction "R2I_8") (pintype "passive"))
    )
    (net (code "121") (name "unconnected-(U3-R2O-Pad9)") (class "Default")
      (node (ref "U3") (pin "9") (pinfunction "R2O_9") (pintype "passive"))
    )
    (net (code "122") (name "unconnected-(U3-T2I-Pad10)") (class "Default")
      (node (ref "U3") (pin "10") (pinfunction "T2I_10") (pintype "passive"))
    )
    (net (code "123") (name "unconnected-(U3-T2O-Pad7)") (class "Default")
      (node (ref "U3") (pin "7") (pinfunction "T2O_7") (pintype "passive"))
    )
  )
)
